# Transinstor_Booster.net
KiCad netlist of a schematic drawn in Altium Designer
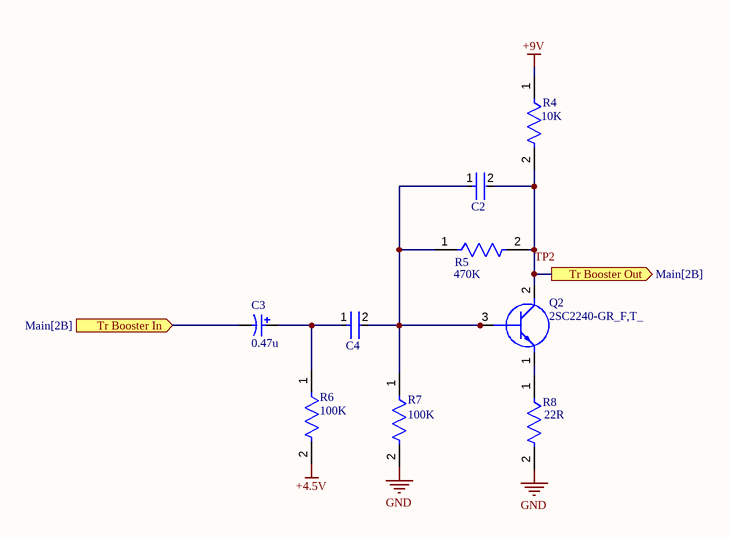
[diagram p0: Transinstor_Booster.SchDoc]

(export (version "E")
  (design (tool "Eeschema 10.0.6"))
  (components
    (comp (ref "C2")
      (value "250p")
      (footprint "FP-RCE1A2-MFG")
      (description "Cap Ceramic 100nF 100V X7R ±10% Radial 2.5mm +125°C Automotive Bulk")
      (fields (field (name "TOLERANCE") "10%"))
      (libsource (lib "Altium Content Vault") (part "02cd4be3c70576c341d710602a673aa"))
    )
    (comp (ref "C3")
      (value "0.47u")
      (footprint "CAPPR55-200-1100X500X1200")
      (description "Aluminum Electrolytic Capacitor, 22 uF, +/- 20%, 50 V, -40 to 85 degC, 2-Pin THD, RoHS, Bulk")
      (fields (field (name "VOLTAGE") "50V") (field (name "MANUFACTURER") "Panasonic"))
      (libsource (lib "Altium Content Vault") (part "CAP-P-2"))
    )
    (comp (ref "C4")
      (value "47n")
      (footprint "FP-RCE1A2-MFG")
      (description "Cap Ceramic 100nF 100V X7R ±10% Radial 2.5mm +125°C Automotive Bulk")
      (fields (field (name "TOLERANCE") "10%"))
      (libsource (lib "Altium Content Vault") (part "02cd4be3c70576c341d710602a673aa"))
    )
    (comp (ref "Q2")
      (value "2SC2240-GR_F,T_")
      (footprint "SamacSys:SSM3K7002CFULF")
      (description "Transistor BJT NPN")
      (fields
        (field (name "MANUFACTURER_PART_NUMBER") "2SC2240-GR(F,T)")
        (field (name "MOUSER PART NUMBER") "757-2SC2240-GRFT")
      )
      (libsource (lib "*") (part "2SC2240-GR_F,T_"))
    )
    (comp (ref "R4")
      (value "10K")
      (footprint "FP-MRS1600-MFG")
      (description "RES 20K OHM 0.4W 1% AXIAL")
      (fields (field (name "TOLERANCE") "1%"))
      (libsource (lib "Altium Content Vault") (part "1029c3af85768c4190bb7ad29bc67b5"))
    )
    (comp (ref "R5")
      (value "470K")
      (footprint "FP-MRS1600-MFG")
      (description "RES 20K OHM 0.4W 1% AXIAL")
      (fields (field (name "TOLERANCE") "1%"))
      (libsource (lib "Altium Content Vault") (part "1029c3af85768c4190bb7ad29bc67b5"))
    )
    (comp (ref "R6")
      (value "100K")
      (footprint "FP-MRS1600-MFG")
      (description "RES 20K OHM 0.4W 1% AXIAL")
      (fields (field (name "TOLERANCE") "1%"))
      (libsource (lib "Altium Content Vault") (part "1029c3af85768c4190bb7ad29bc67b5"))
    )
    (comp (ref "R7")
      (value "100K")
      (footprint "FP-MRS1600-MFG")
      (description "RES 20K OHM 0.4W 1% AXIAL")
      (fields (field (name "TOLERANCE") "1%"))
      (libsource (lib "Altium Content Vault") (part "1029c3af85768c4190bb7ad29bc67b5"))
    )
    (comp (ref "R8")
      (value "22R")
      (footprint "FP-MRS1600-MFG")
      (description "RES 20K OHM 0.4W 1% AXIAL")
      (fields (field (name "TOLERANCE") "1%"))
      (libsource (lib "Altium Content Vault") (part "1029c3af85768c4190bb7ad29bc67b5"))
    )
  )
  (nets
    (net (code "1") (name "+4.5V") (class "Default")
      (node (ref "R6") (pin "2") (pinfunction "2_2") (pintype "passive"))
    )
    (net (code "2") (name "+9V") (class "Default")
      (node (ref "R4") (pin "1") (pinfunction "1_1") (pintype "passive"))
    )
    (net (code "3") (name "/TP2") (class "Default")
      (node (ref "C2") (pin "2") (pinfunction "2_2") (pintype "passive"))
      (node (ref "Q2") (pin "2") (pinfunction "C_2") (pintype "passive"))
      (node (ref "R4") (pin "2") (pinfunction "2_2") (pintype "passive"))
      (node (ref "R5") (pin "2") (pinfunction "2_2") (pintype "passive"))
    )
    (net (code "4") (name "/Tr Booster In") (class "Default")
      (node (ref "C3") (pin "2") (pinfunction "2_2") (pintype "passive"))
    )
    (net (code "5") (name "GND") (class "Default")
      (node (ref "R7") (pin "2") (pinfunction "2_2") (pintype "passive"))
      (node (ref "R8") (pin "2") (pinfunction "2_2") (pintype "passive"))
    )
    (net (code "6") (name "Net-(C3-Pad1)") (class "Default")
      (node (ref "C3") (pin "1") (pinfunction "1_1") (pintype "passive"))
      (node (ref "C4") (pin "1") (pinfunction "1_1") (pintype "passive"))
      (node (ref "R6") (pin "1") (pinfunction "1_1") (pintype "passive"))
    )
    (net (code "7") (name "Net-(Q2-B)") (class "Default")
      (node (ref "C2") (pin "1") (pinfunction "1_1") (pintype "passive"))
      (node (ref "C4") (pin "2") (pinfunction "2_2") (pintype "passive"))
      (node (ref "Q2") (pin "3") (pinfunction "B_3") (pintype "passive"))
      (node (ref "R5") (pin "1") (pinfunction "1_1") (pintype "passive"))
      (node (ref "R7") (pin "1") (pinfunction "1_1") (pintype "passive"))
    )
    (net (code "8") (name "Net-(Q2-E)") (class "Default")
      (node (ref "Q2") (pin "1") (pinfunction "E_1") (pintype "passive"))
      (node (ref "R8") (pin "1") (pinfunction "1_1") (pintype "passive"))
    )
  )
)
